# usb_lir2456_charger.net
KiCad netlist of a schematic drawn in EAGLE
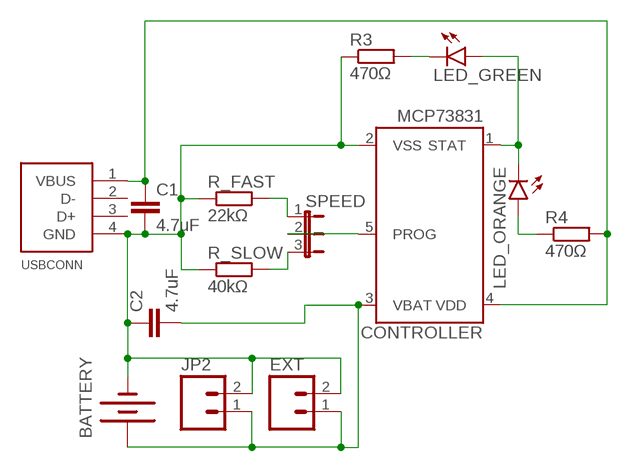
[diagram p0: schematic, sheet 1]

(export (version "E")
  (design (tool "Eeschema 10.0.6"))
  (components
    (comp (ref "BATTERY")
      (value "BATTERY20PTH")
      (footprint "eagle-import:BATTCOM_20MM_PTH")
      (libsource (lib "eagle-import") (part "BATTERY20PTH"))
    )
    (comp (ref "C1")
      (value "4.7uF")
      (footprint "eagle-import:C0805")
      (libsource (lib "eagle-import") (part "C"))
    )
    (comp (ref "C2")
      (value "4.7uF")
      (footprint "eagle-import:C0805")
      (libsource (lib "eagle-import") (part "C"))
    )
    (comp (ref "CONTROLLER")
      (value "MCP73831")
      (footprint "eagle-import:SOT23-5")
      (libsource (lib "eagle-import") (part "MCP73831"))
    )
    (comp (ref "EXT")
      (value "M02PTH")
      (footprint "eagle-import:1X02")
      (libsource (lib "eagle-import") (part "M02PTH"))
    )
    (comp (ref "JP2")
      (value "M02JST-PTH-VERT")
      (footprint "eagle-import:JST-2-PTH-VERT")
      (libsource (lib "eagle-import") (part "M02JST-PTH-VERT"))
    )
    (comp (ref "LED_GREEN")
      (value "LED0603")
      (footprint "eagle-import:LED-0603")
      (libsource (lib "eagle-import") (part "LED0603"))
    )
    (comp (ref "LED_ORANGE")
      (value "LED0603")
      (footprint "eagle-import:LED-0603")
      (libsource (lib "eagle-import") (part "LED0603"))
    )
    (comp (ref "R3")
      (value "470Ω")
      (footprint "eagle-import:R0805")
      (libsource (lib "eagle-import") (part "R"))
    )
    (comp (ref "R4")
      (value "470Ω")
      (footprint "eagle-import:R0805")
      (libsource (lib "eagle-import") (part "R"))
    )
    (comp (ref "R_FAST")
      (value "22kΩ")
      (footprint "eagle-import:R0805")
      (libsource (lib "eagle-import") (part "R"))
    )
    (comp (ref "R_SLOW")
      (value "40kΩ")
      (footprint "eagle-import:R0805")
      (libsource (lib "eagle-import") (part "R"))
    )
    (comp (ref "SPEED")
      (value "JP2E")
      (footprint "eagle-import:JP2")
      (libsource (lib "eagle-import") (part "JP2E"))
    )
    (comp (ref "USBCONN")
      (value "USB-CON-4PIN")
      (footprint "eagle-import:USB-MALE-A-PCB")
      (libsource (lib "eagle-import") (part "USB-CON-4PIN"))
    )
  )
  (nets
    (net (code "1") (name "Net-(BATTERY-+)") (class "Default")
      (node (ref "BATTERY") (pin "1") (pinfunction "+_1") (pintype "power_in"))
      (node (ref "C2") (pin "2") (pinfunction "2_2") (pintype "passive"))
      (node (ref "CONTROLLER") (pin "3") (pinfunction "VBAT_3") (pintype "power_in"))
      (node (ref "EXT") (pin "1") (pinfunction "1_1") (pintype "passive"))
      (node (ref "JP2") (pin "1") (pinfunction "1_1") (pintype "passive"))
    )
    (net (code "2") (name "Net-(BATTERY--)") (class "Default")
      (node (ref "BATTERY") (pin "2") (pinfunction "-_2") (pintype "power_in"))
      (node (ref "C1") (pin "2") (pinfunction "2_2") (pintype "passive"))
      (node (ref "C2") (pin "1") (pinfunction "1_1") (pintype "passive"))
      (node (ref "CONTROLLER") (pin "2") (pinfunction "VSS_2") (pintype "power_in"))
      (node (ref "EXT") (pin "2") (pinfunction "2_2") (pintype "passive"))
      (node (ref "JP2") (pin "2") (pinfunction "2_2") (pintype "passive"))
      (node (ref "R3") (pin "1") (pinfunction "1_1") (pintype "passive"))
      (node (ref "R_FAST") (pin "1") (pinfunction "1_1") (pintype "passive"))
      (node (ref "R_SLOW") (pin "1") (pinfunction "1_1") (pintype "passive"))
      (node (ref "USBCONN") (pin "4") (pinfunction "GND_4") (pintype "power_in"))
    )
    (net (code "3") (name "Net-(CONTROLLER-PROG)") (class "Default")
      (node (ref "CONTROLLER") (pin "5") (pinfunction "PROG_5") (pintype "input"))
      (node (ref "SPEED") (pin "2") (pinfunction "2_2") (pintype "passive"))
    )
    (net (code "4") (name "Net-(CONTROLLER-STAT)") (class "Default")
      (node (ref "CONTROLLER") (pin "1") (pinfunction "STAT_1") (pintype "output"))
      (node (ref "LED_GREEN") (pin "A") (pinfunction "A_A") (pintype "passive"))
      (node (ref "LED_ORANGE") (pin "C") (pinfunction "C_C") (pintype "passive"))
    )
    (net (code "5") (name "Net-(CONTROLLER-VDD)") (class "Default")
      (node (ref "C1") (pin "1") (pinfunction "1_1") (pintype "passive"))
      (node (ref "CONTROLLER") (pin "4") (pinfunction "VDD_4") (pintype "power_in"))
      (node (ref "R4") (pin "2") (pinfunction "2_2") (pintype "passive"))
      (node (ref "USBCONN") (pin "1") (pinfunction "VBUS_1") (pintype "power_in"))
    )
    (net (code "6") (name "Net-(LED_GREEN-PadC)") (class "Default")
      (node (ref "LED_GREEN") (pin "C") (pinfunction "C_C") (pintype "passive"))
      (node (ref "R3") (pin "2") (pinfunction "2_2") (pintype "passive"))
    )
    (net (code "7") (name "Net-(LED_ORANGE-PadA)") (class "Default")
      (node (ref "LED_ORANGE") (pin "A") (pinfunction "A_A") (pintype "passive"))
      (node (ref "R4") (pin "1") (pinfunction "1_1") (pintype "passive"))
    )
    (net (code "8") (name "Net-(R_FAST-Pad2)") (class "Default")
      (node (ref "R_FAST") (pin "2") (pinfunction "2_2") (pintype "passive"))
      (node (ref "SPEED") (pin "1") (pinfunction "1_1") (pintype "passive"))
    )
    (net (code "9") (name "Net-(R_SLOW-Pad2)") (class "Default")
      (node (ref "R_SLOW") (pin "2") (pinfunction "2_2") (pintype "passive"))
      (node (ref "SPEED") (pin "3") (pinfunction "3_3") (pintype "passive"))
    )
    (net (code "10") (name "unconnected-(USBCONN-D+-Pad3)") (class "Default")
      (node (ref "USBCONN") (pin "3") (pinfunction "D+_3") (pintype "bidirectional"))
    )
    (net (code "11") (name "unconnected-(USBCONN-D--Pad2)") (class "Default")
      (node (ref "USBCONN") (pin "2") (pinfunction "D-_2") (pintype "bidirectional"))
    )
  )
)
